# main_sheet.net
KiCad netlist of a schematic drawn in Altium Designer
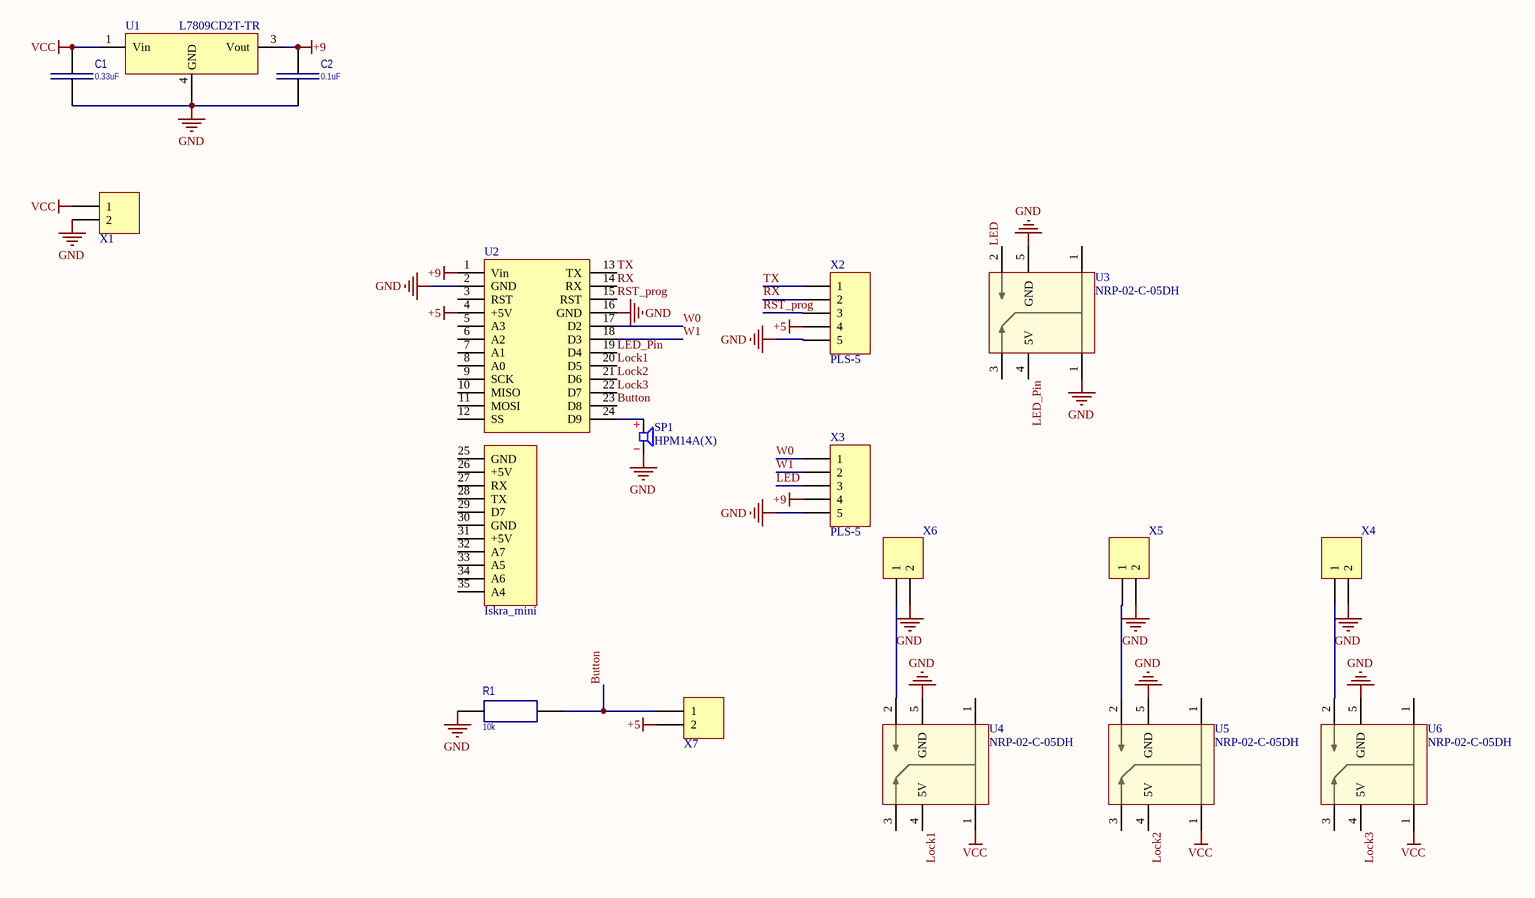
[diagram p0: main_sheet.SchDoc]

(export (version "E")
  (design (tool "Eeschema 10.0.6"))
  (components
    (comp (ref "C1")
      (value "0.33uF")
      (footprint "C_0805")
      (description "Capacitor")
      (libsource (lib "AX_Altium_v2.3") (part "C0805"))
    )
    (comp (ref "C2")
      (value "0.1uF")
      (footprint "C_0805")
      (description "Capacitor")
      (libsource (lib "AX_Altium_v2.3") (part "C0805"))
    )
    (comp (ref "R1")
      (value "10k")
      (footprint "R_0805")
      (description "Resistor")
      (libsource (lib "AX_Altium_v2.3") (part "R0805"))
    )
    (comp (ref "SP1")
      (value "HPM14A(X)")
      (footprint "Beeper_14x7.5")
      (description "Speaker with (AX)/without (A) frequency grnerator")
      (libsource (lib "AX_Altium_v2.3") (part "HPM14A(X)"))
    )
    (comp (ref "U1")
      (value "L7809CD2T-TR")
      (footprint "*VREG_L7805ACD2T")
      (libsource (lib "LDO") (part "L7809CD2T-TR"))
    )
    (comp (ref "U2")
      (value "Iskra_mini")
      (footprint "ISKRA_MINI_L")
      (libsource (lib "Arduino") (part "Iskra_mini"))
    )
    (comp (ref "U3") (value "NRP-02-C-05DH") (footprint "Relay 5V") (libsource (lib "relay") (part "Relay")))
    (comp (ref "U4") (value "NRP-02-C-05DH") (footprint "Relay 5V") (libsource (lib "relay") (part "Relay")))
    (comp (ref "U5") (value "NRP-02-C-05DH") (footprint "Relay 5V") (libsource (lib "relay") (part "Relay")))
    (comp (ref "U6") (value "NRP-02-C-05DH") (footprint "Relay 5V") (libsource (lib "relay") (part "Relay")))
    (comp (ref "X1")
      (value "PLS-2")
      (footprint "DG142R-5.08-02P-14")
      (description "Header, 2-Pin")
      (fields (field (name "PUBLISHER") "Altium Limited"))
      (libsource (lib "") (part "PLS-2_1"))
    )
    (comp (ref "X2")
      (value "PLS-5")
      (footprint "PLS-5-3D")
      (description "Header, 5-Pin")
      (fields (field (name "PUBLISHER") "Altium Limited"))
      (libsource (lib "ConnectorButtonSocetDisplay") (part "PLS-5"))
    )
    (comp (ref "X3")
      (value "PLS-5")
      (footprint "PLS-5-3D")
      (description "Header, 5-Pin")
      (fields (field (name "PUBLISHER") "Altium Limited"))
      (libsource (lib "ConnectorButtonSocetDisplay") (part "PLS-5"))
    )
    (comp (ref "X4")
      (value "PLS-2")
      (footprint "DG142R-5.08-02P-14")
      (description "Header, 2-Pin")
      (fields (field (name "PUBLISHER") "Altium Limited"))
      (libsource (lib "ConnectorButtonSocetDisplay") (part "PLS-2"))
    )
    (comp (ref "X5")
      (value "PLS-2")
      (footprint "DG142R-5.08-02P-14")
      (description "Header, 2-Pin")
      (fields (field (name "PUBLISHER") "Altium Limited"))
      (libsource (lib "ConnectorButtonSocetDisplay") (part "PLS-2"))
    )
    (comp (ref "X6")
      (value "PLS-2")
      (footprint "DG142R-5.08-02P-14")
      (description "Header, 2-Pin")
      (fields (field (name "PUBLISHER") "Altium Limited"))
      (libsource (lib "ConnectorButtonSocetDisplay") (part "PLS-2"))
    )
    (comp (ref "X7")
      (value "PLS-2")
      (footprint "PLS-2-3D")
      (description "Header, 2-Pin")
      (fields (field (name "PUBLISHER") "Altium Limited"))
      (libsource (lib "") (part "PLS-2_1"))
    )
  )
  (nets
    (net (code "1") (name "+5") (class "Default")
      (node (ref "U2") (pin "4") (pinfunction "+5V_4") (pintype "passive"))
      (node (ref "X2") (pin "4") (pinfunction "4_4") (pintype "passive"))
      (node (ref "X7") (pin "2") (pinfunction "2_2") (pintype "passive"))
    )
    (net (code "2") (name "+9") (class "Default")
      (node (ref "C2") (pin "2") (pinfunction "2_2") (pintype "passive"))
      (node (ref "U1") (pin "3") (pinfunction "Vout_3") (pintype "passive"))
      (node (ref "U2") (pin "1") (pinfunction "Vin_1") (pintype "passive"))
      (node (ref "X3") (pin "4") (pinfunction "4_4") (pintype "passive"))
    )
    (net (code "3") (name "/Button") (class "Default")
      (node (ref "R1") (pin "2") (pinfunction "2_2") (pintype "passive"))
      (node (ref "U2") (pin "23") (pinfunction "D8_23") (pintype "passive"))
      (node (ref "X7") (pin "1") (pinfunction "1_1") (pintype "passive"))
    )
    (net (code "4") (name "/LED") (class "Default")
      (node (ref "U3") (pin "2") (pintype "passive"))
      (node (ref "X3") (pin "3") (pinfunction "3_3") (pintype "passive"))
    )
    (net (code "5") (name "/LED_Pin") (class "Default")
      (node (ref "U2") (pin "19") (pinfunction "D4_19") (pintype "passive"))
      (node (ref "U3") (pin "4") (pinfunction "5V_4") (pintype "passive"))
    )
    (net (code "6") (name "/Lock1") (class "Default")
      (node (ref "U2") (pin "20") (pinfunction "D5_20") (pintype "passive"))
      (node (ref "U4") (pin "4") (pinfunction "5V_4") (pintype "passive"))
    )
    (net (code "7") (name "/Lock2") (class "Default")
      (node (ref "U2") (pin "21") (pinfunction "D6_21") (pintype "passive"))
      (node (ref "U5") (pin "4") (pinfunction "5V_4") (pintype "passive"))
    )
    (net (code "8") (name "/Lock3") (class "Default")
      (node (ref "U2") (pin "22") (pinfunction "D7_22") (pintype "passive"))
      (node (ref "U6") (pin "4") (pinfunction "5V_4") (pintype "passive"))
    )
    (net (code "9") (name "/RST_prog") (class "Default")
      (node (ref "U2") (pin "15") (pinfunction "RST_15") (pintype "passive"))
      (node (ref "X2") (pin "3") (pinfunction "3_3") (pintype "passive"))
    )
    (net (code "10") (name "/RX") (class "Default")
      (node (ref "U2") (pin "14") (pinfunction "RX_14") (pintype "passive"))
      (node (ref "X2") (pin "2") (pinfunction "2_2") (pintype "passive"))
    )
    (net (code "11") (name "/TX") (class "Default")
      (node (ref "U2") (pin "13") (pinfunction "TX_13") (pintype "passive"))
      (node (ref "X2") (pin "1") (pinfunction "1_1") (pintype "passive"))
    )
    (net (code "12") (name "/W0") (class "Default")
      (node (ref "U2") (pin "17") (pinfunction "D2_17") (pintype "passive"))
      (node (ref "X3") (pin "1") (pinfunction "1_1") (pintype "passive"))
    )
    (net (code "13") (name "/W1") (class "Default")
      (node (ref "U2") (pin "18") (pinfunction "D3_18") (pintype "passive"))
      (node (ref "X3") (pin "2") (pinfunction "2_2") (pintype "passive"))
    )
    (net (code "14") (name "GND") (class "Default")
      (node (ref "C1") (pin "1") (pinfunction "1_1") (pintype "passive"))
      (node (ref "C2") (pin "1") (pinfunction "1_1") (pintype "passive"))
      (node (ref "R1") (pin "1") (pinfunction "1_1") (pintype "passive"))
      (node (ref "SP1") (pin "2") (pinfunction "-_2") (pintype "passive"))
      (node (ref "U1") (pin "4") (pinfunction "GND_4") (pintype "passive"))
      (node (ref "U2") (pin "16") (pinfunction "GND_16") (pintype "passive"))
      (node (ref "U2") (pin "2") (pinfunction "GND_2") (pintype "passive"))
      (node (ref "U3") (pin "1") (pintype "passive"))
      (node (ref "U3") (pin "5") (pinfunction "_GND_5") (pintype "passive"))
      (node (ref "U4") (pin "5") (pinfunction "_GND_5") (pintype "passive"))
      (node (ref "U5") (pin "5") (pinfunction "_GND_5") (pintype "passive"))
      (node (ref "U6") (pin "5") (pinfunction "_GND_5") (pintype "passive"))
      (node (ref "X1") (pin "2") (pinfunction "2_2") (pintype "passive"))
      (node (ref "X2") (pin "5") (pinfunction "5_5") (pintype "passive"))
      (node (ref "X3") (pin "5") (pinfunction "5_5") (pintype "passive"))
      (node (ref "X4") (pin "2") (pinfunction "2_2") (pintype "passive"))
      (node (ref "X5") (pin "2") (pinfunction "2_2") (pintype "passive"))
      (node (ref "X6") (pin "2") (pinfunction "2_2") (pintype "passive"))
    )
    (net (code "15") (name "Net-(SP1-+)") (class "Default")
      (node (ref "SP1") (pin "1") (pinfunction "+_1") (pintype "passive"))
      (node (ref "U2") (pin "24") (pinfunction "D9_24") (pintype "passive"))
    )
    (net (code "16") (name "Net-(U4-Pad2)") (class "Default")
      (node (ref "U4") (pin "2") (pintype "passive"))
      (node (ref "X6") (pin "1") (pinfunction "1_1") (pintype "passive"))
    )
    (net (code "17") (name "Net-(U5-Pad2)") (class "Default")
      (node (ref "U5") (pin "2") (pintype "passive"))
      (node (ref "X5") (pin "1") (pinfunction "1_1") (pintype "passive"))
    )
    (net (code "18") (name "Net-(U6-Pad2)") (class "Default")
      (node (ref "U6") (pin "2") (pintype "passive"))
      (node (ref "X4") (pin "1") (pinfunction "1_1") (pintype "passive"))
    )
    (net (code "19") (name "VCC") (class "Default")
      (node (ref "C1") (pin "2") (pinfunction "2_2") (pintype "passive"))
      (node (ref "U1") (pin "1") (pinfunction "Vin_1") (pintype "passive"))
      (node (ref "U4") (pin "1") (pintype "passive"))
      (node (ref "U5") (pin "1") (pintype "passive"))
      (node (ref "U6") (pin "1") (pintype "passive"))
      (node (ref "X1") (pin "1") (pinfunction "1_1") (pintype "passive"))
    )
    (net (code "20") (name "unconnected-(U2-+5V-Pad26)") (class "Default")
      (node (ref "U2") (pin "26") (pinfunction "+5V_26") (pintype "passive"))
    )
    (net (code "21") (name "unconnected-(U2-+5V-Pad31)") (class "Default")
      (node (ref "U2") (pin "31") (pinfunction "+5V_31") (pintype "passive"))
    )
    (net (code "22") (name "unconnected-(U2-A0-Pad8)") (class "Default")
      (node (ref "U2") (pin "8") (pinfunction "A0_8") (pintype "passive"))
    )
    (net (code "23") (name "unconnected-(U2-A1-Pad7)") (class "Default")
      (node (ref "U2") (pin "7") (pinfunction "A1_7") (pintype "passive"))
    )
    (net (code "24") (name "unconnected-(U2-A2-Pad6)") (class "Default")
      (node (ref "U2") (pin "6") (pinfunction "A2_6") (pintype "passive"))
    )
    (net (code "25") (name "unconnected-(U2-A3-Pad5)") (class "Default")
      (node (ref "U2") (pin "5") (pinfunction "A3_5") (pintype "passive"))
    )
    (net (code "26") (name "unconnected-(U2-A4-Pad35)") (class "Default")
      (node (ref "U2") (pin "35") (pinfunction "A4_35") (pintype "passive"))
    )
    (net (code "27") (name "unconnected-(U2-A5-Pad33)") (class "Default")
      (node (ref "U2") (pin "33") (pinfunction "A5_33") (pintype "passive"))
    )
    (net (code "28") (name "unconnected-(U2-A6-Pad34)") (class "Default")
      (node (ref "U2") (pin "34") (pinfunction "A6_34") (pintype "passive"))
    )
    (net (code "29") (name "unconnected-(U2-A7-Pad32)") (class "Default")
      (node (ref "U2") (pin "32") (pinfunction "A7_32") (pintype "passive"))
    )
    (net (code "30") (name "unconnected-(U2-D7-Pad29)") (class "Default")
      (node (ref "U2") (pin "29") (pinfunction "D7_29") (pintype "passive"))
    )
    (net (code "31") (name "unconnected-(U2-GND-Pad25)") (class "Default")
      (node (ref "U2") (pin "25") (pinfunction "GND_25") (pintype "passive"))
    )
    (net (code "32") (name "unconnected-(U2-GND-Pad30)") (class "Default")
      (node (ref "U2") (pin "30") (pinfunction "GND_30") (pintype "passive"))
    )
    (net (code "33") (name "unconnected-(U2-MISO-Pad10)") (class "Default")
      (node (ref "U2") (pin "10") (pinfunction "MISO_10") (pintype "passive"))
    )
    (net (code "34") (name "unconnected-(U2-MOSI-Pad11)") (class "Default")
      (node (ref "U2") (pin "11") (pinfunction "MOSI_11") (pintype "passive"))
    )
    (net (code "35") (name "unconnected-(U2-RST-Pad3)") (class "Default")
      (node (ref "U2") (pin "3") (pinfunction "RST_3") (pintype "passive"))
    )
    (net (code "36") (name "unconnected-(U2-RX-Pad27)") (class "Default")
      (node (ref "U2") (pin "27") (pinfunction "RX_27") (pintype "passive"))
    )
    (net (code "37") (name "unconnected-(U2-SCK-Pad9)") (class "Default")
      (node (ref "U2") (pin "9") (pinfunction "SCK_9") (pintype "passive"))
    )
    (net (code "38") (name "unconnected-(U2-SS-Pad12)") (class "Default")
      (node (ref "U2") (pin "12") (pinfunction "SS_12") (pintype "passive"))
    )
    (net (code "39") (name "unconnected-(U2-TX-Pad28)") (class "Default")
      (node (ref "U2") (pin "28") (pinfunction "TX_28") (pintype "passive"))
    )
    (net (code "40") (name "unconnected-(U3-Pad1)") (class "Default")
      (node (ref "U3") (pin "1") (pintype "passive"))
    )
    (net (code "41") (name "unconnected-(U3-Pad3)") (class "Default")
      (node (ref "U3") (pin "3") (pintype "passive"))
    )
    (net (code "42") (name "unconnected-(U4-Pad1)") (class "Default")
      (node (ref "U4") (pin "1") (pintype "passive"))
    )
    (net (code "43") (name "unconnected-(U4-Pad3)") (class "Default")
      (node (ref "U4") (pin "3") (pintype "passive"))
    )
    (net (code "44") (name "unconnected-(U5-Pad1)") (class "Default")
      (node (ref "U5") (pin "1") (pintype "passive"))
    )
    (net (code "45") (name "unconnected-(U5-Pad3)") (class "Default")
      (node (ref "U5") (pin "3") (pintype "passive"))
    )
    (net (code "46") (name "unconnected-(U6-Pad1)") (class "Default")
      (node (ref "U6") (pin "1") (pintype "passive"))
    )
    (net (code "47") (name "unconnected-(U6-Pad3)") (class "Default")
      (node (ref "U6") (pin "3") (pintype "passive"))
    )
  )
)
